# Simple-Charger-LiIon-OpampBased-LM324-pr.net
KiCad netlist of a schematic drawn in EAGLE
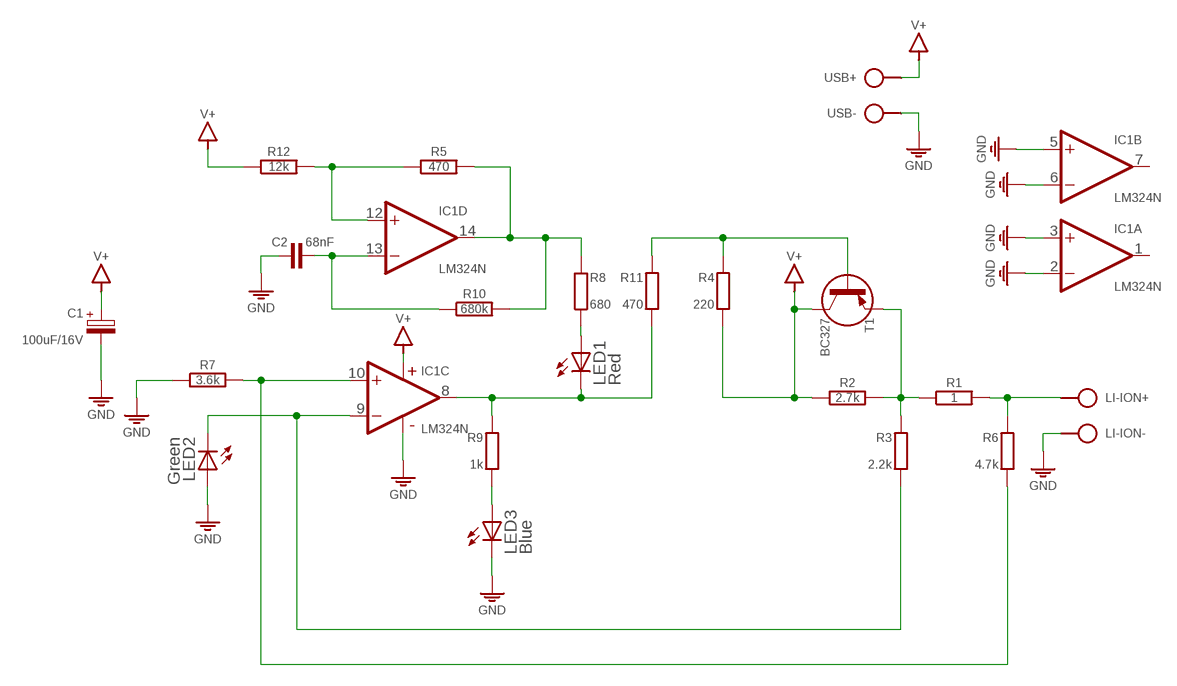
[diagram p0: schematic, sheet 1]

(export (version "E")
  (design (tool "Eeschema 10.0.6"))
  (components
    (comp (ref "C1")
      (value "100uF/16V")
      (footprint "eagle-import:E2,5-5_V")
      (libsource (lib "eagle-import") (part "CPOLE2,5-5/V"))
    )
    (comp (ref "C2")
      (value "68nF")
      (footprint "eagle-import:C050-020X044_V")
      (libsource (lib "eagle-import") (part "C-H050-020X044/V"))
    )
    (comp (ref "IC1")
      (value "LM324N")
      (footprint "eagle-import:DIL14")
      (libsource (lib "eagle-import") (part "LM324N"))
    )
    (comp (ref "LED1")
      (value "Red")
      (footprint "eagle-import:LED3MM")
      (libsource (lib "eagle-import") (part "LED3MM"))
    )
    (comp (ref "LED2")
      (value "Green")
      (footprint "eagle-import:LED3MM")
      (libsource (lib "eagle-import") (part "LED3MM"))
    )
    (comp (ref "LED3")
      (value "Blue")
      (footprint "eagle-import:LED3MM")
      (libsource (lib "eagle-import") (part "LED3MM"))
    )
    (comp (ref "LI-ION")
      (value "SPAD+-+-")
      (footprint "eagle-import:SPAD+-")
      (libsource (lib "eagle-import") (part "SPAD+-+-"))
    )
    (comp (ref "R1")
      (value "1")
      (footprint "eagle-import:0204_10-V")
      (libsource (lib "eagle-import") (part "R-H0204/10-V"))
    )
    (comp (ref "R2")
      (value "2.7k")
      (footprint "eagle-import:0204_10-V")
      (libsource (lib "eagle-import") (part "R-H0204/10-V"))
    )
    (comp (ref "R3")
      (value "2.2k")
      (footprint "eagle-import:0204_10-V")
      (libsource (lib "eagle-import") (part "R0204/10-V"))
    )
    (comp (ref "R4")
      (value "220")
      (footprint "eagle-import:0204_10")
      (libsource (lib "eagle-import") (part "R0204/10"))
    )
    (comp (ref "R5")
      (value "470")
      (footprint "eagle-import:0204_10")
      (libsource (lib "eagle-import") (part "R-H0204/10"))
    )
    (comp (ref "R6")
      (value "4.7k")
      (footprint "eagle-import:0204_10-V")
      (libsource (lib "eagle-import") (part "R0204/10-V"))
    )
    (comp (ref "R7")
      (value "3.6k")
      (footprint "eagle-import:0204_10-V")
      (libsource (lib "eagle-import") (part "R-H0204/10-V"))
    )
    (comp (ref "R8")
      (value "680")
      (footprint "eagle-import:0204_10")
      (libsource (lib "eagle-import") (part "R0204/10"))
    )
    (comp (ref "R9")
      (value "1k")
      (footprint "eagle-import:0204_10-V")
      (libsource (lib "eagle-import") (part "R0204/10-V"))
    )
    (comp (ref "R10")
      (value "680k")
      (footprint "eagle-import:0204_2V")
      (libsource (lib "eagle-import") (part "R-H0204/2V"))
    )
    (comp (ref "R11")
      (value "470")
      (footprint "eagle-import:0204_10-V")
      (libsource (lib "eagle-import") (part "R0204/10-V"))
    )
    (comp (ref "R12")
      (value "12k")
      (footprint "eagle-import:0204_10-V")
      (libsource (lib "eagle-import") (part "R-H0204/10-V"))
    )
    (comp (ref "T1")
      (value "BC327")
      (footprint "eagle-import:TO92")
      (libsource (lib "eagle-import") (part "BC327"))
    )
    (comp (ref "USB")
      (value "SPAD+--+")
      (footprint "eagle-import:SPAD-+")
      (libsource (lib "eagle-import") (part "SPAD+--+"))
    )
  )
  (nets
    (net (code "1") (name "GND") (class "Default")
      (node (ref "C1") (pin "-") (pinfunction "-_-") (pintype "passive"))
      (node (ref "C2") (pin "1") (pinfunction "1_1") (pintype "passive"))
      (node (ref "IC1") (pin "11") (pinfunction "V-_11") (pintype "power_in"))
      (node (ref "IC1") (pin "2") (pinfunction "-IN_2") (pintype "input"))
      (node (ref "IC1") (pin "3") (pinfunction "+IN_3") (pintype "input"))
      (node (ref "IC1") (pin "5") (pinfunction "+IN_5") (pintype "input"))
      (node (ref "IC1") (pin "6") (pinfunction "-IN_6") (pintype "input"))
      (node (ref "LED2") (pin "A") (pinfunction "A_A") (pintype "passive"))
      (node (ref "LED3") (pin "K") (pinfunction "C_K") (pintype "passive"))
      (node (ref "LI-ION") (pin "1") (pinfunction "P$1_1") (pintype "passive"))
      (node (ref "R7") (pin "1") (pinfunction "1_1") (pintype "passive"))
      (node (ref "USB") (pin "1") (pinfunction "P$1_1") (pintype "passive"))
    )
    (net (code "2") (name "Net-(IC1C-+IN)") (class "Default")
      (node (ref "IC1") (pin "10") (pinfunction "+IN_10") (pintype "input"))
      (node (ref "R6") (pin "2") (pinfunction "2_2") (pintype "passive"))
      (node (ref "R7") (pin "2") (pinfunction "2_2") (pintype "passive"))
    )
    (net (code "3") (name "Net-(IC1C--IN)") (class "Default")
      (node (ref "IC1") (pin "9") (pinfunction "-IN_9") (pintype "input"))
      (node (ref "LED2") (pin "K") (pinfunction "C_K") (pintype "passive"))
      (node (ref "R3") (pin "2") (pinfunction "2_2") (pintype "passive"))
    )
    (net (code "4") (name "Net-(IC1C-OUT)") (class "Default")
      (node (ref "IC1") (pin "8") (pinfunction "OUT_8") (pintype "output"))
      (node (ref "LED1") (pin "K") (pinfunction "C_K") (pintype "passive"))
      (node (ref "R11") (pin "2") (pinfunction "2_2") (pintype "passive"))
      (node (ref "R9") (pin "1") (pinfunction "1_1") (pintype "passive"))
    )
    (net (code "5") (name "Net-(IC1D-+IN)") (class "Default")
      (node (ref "IC1") (pin "12") (pinfunction "+IN_12") (pintype "input"))
      (node (ref "R12") (pin "2") (pinfunction "2_2") (pintype "passive"))
      (node (ref "R5") (pin "1") (pinfunction "1_1") (pintype "passive"))
    )
    (net (code "6") (name "Net-(IC1D--IN)") (class "Default")
      (node (ref "C2") (pin "2") (pinfunction "2_2") (pintype "passive"))
      (node (ref "IC1") (pin "13") (pinfunction "-IN_13") (pintype "input"))
      (node (ref "R10") (pin "1") (pinfunction "1_1") (pintype "passive"))
    )
    (net (code "7") (name "Net-(IC1D-OUT)") (class "Default")
      (node (ref "IC1") (pin "14") (pinfunction "OUT_14") (pintype "output"))
      (node (ref "R10") (pin "2") (pinfunction "2_2") (pintype "passive"))
      (node (ref "R5") (pin "2") (pinfunction "2_2") (pintype "passive"))
      (node (ref "R8") (pin "1") (pinfunction "1_1") (pintype "passive"))
    )
    (net (code "8") (name "Net-(LED1-PadA)") (class "Default")
      (node (ref "LED1") (pin "A") (pinfunction "A_A") (pintype "passive"))
      (node (ref "R8") (pin "2") (pinfunction "2_2") (pintype "passive"))
    )
    (net (code "9") (name "Net-(LED3-PadA)") (class "Default")
      (node (ref "LED3") (pin "A") (pinfunction "A_A") (pintype "passive"))
      (node (ref "R9") (pin "2") (pinfunction "2_2") (pintype "passive"))
    )
    (net (code "10") (name "Net-(LI-IONA-P$1)") (class "Default")
      (node (ref "LI-ION") (pin "2") (pinfunction "P$1_2") (pintype "passive"))
      (node (ref "R1") (pin "2") (pinfunction "2_2") (pintype "passive"))
      (node (ref "R6") (pin "1") (pinfunction "1_1") (pintype "passive"))
    )
    (net (code "11") (name "Net-(T1-B)") (class "Default")
      (node (ref "R11") (pin "1") (pinfunction "1_1") (pintype "passive"))
      (node (ref "R4") (pin "1") (pinfunction "1_1") (pintype "passive"))
      (node (ref "T1") (pin "2") (pinfunction "B_2") (pintype "passive"))
    )
    (net (code "12") (name "Net-(T1-E)") (class "Default")
      (node (ref "R1") (pin "1") (pinfunction "1_1") (pintype "passive"))
      (node (ref "R2") (pin "2") (pinfunction "2_2") (pintype "passive"))
      (node (ref "R3") (pin "1") (pinfunction "1_1") (pintype "passive"))
      (node (ref "T1") (pin "3") (pinfunction "E_3") (pintype "passive"))
    )
    (net (code "13") (name "V+") (class "Default")
      (node (ref "C1") (pin "+") (pinfunction "+_+") (pintype "passive"))
      (node (ref "IC1") (pin "4") (pinfunction "V+_4") (pintype "power_in"))
      (node (ref "R12") (pin "1") (pinfunction "1_1") (pintype "passive"))
      (node (ref "R2") (pin "1") (pinfunction "1_1") (pintype "passive"))
      (node (ref "R4") (pin "2") (pinfunction "2_2") (pintype "passive"))
      (node (ref "T1") (pin "1") (pinfunction "C_1") (pintype "passive"))
      (node (ref "USB") (pin "2") (pinfunction "P$1_2") (pintype "passive"))
    )
    (net (code "14") (name "unconnected-(IC1A-OUT-Pad1)") (class "Default")
      (node (ref "IC1") (pin "1") (pinfunction "OUT_1") (pintype "output"))
    )
    (net (code "15") (name "unconnected-(IC1B-OUT-Pad7)") (class "Default")
      (node (ref "IC1") (pin "7") (pinfunction "OUT_7") (pintype "output"))
    )
  )
)
